# Led_panel_0_2.net
KiCad netlist of a schematic drawn in Altium Designer
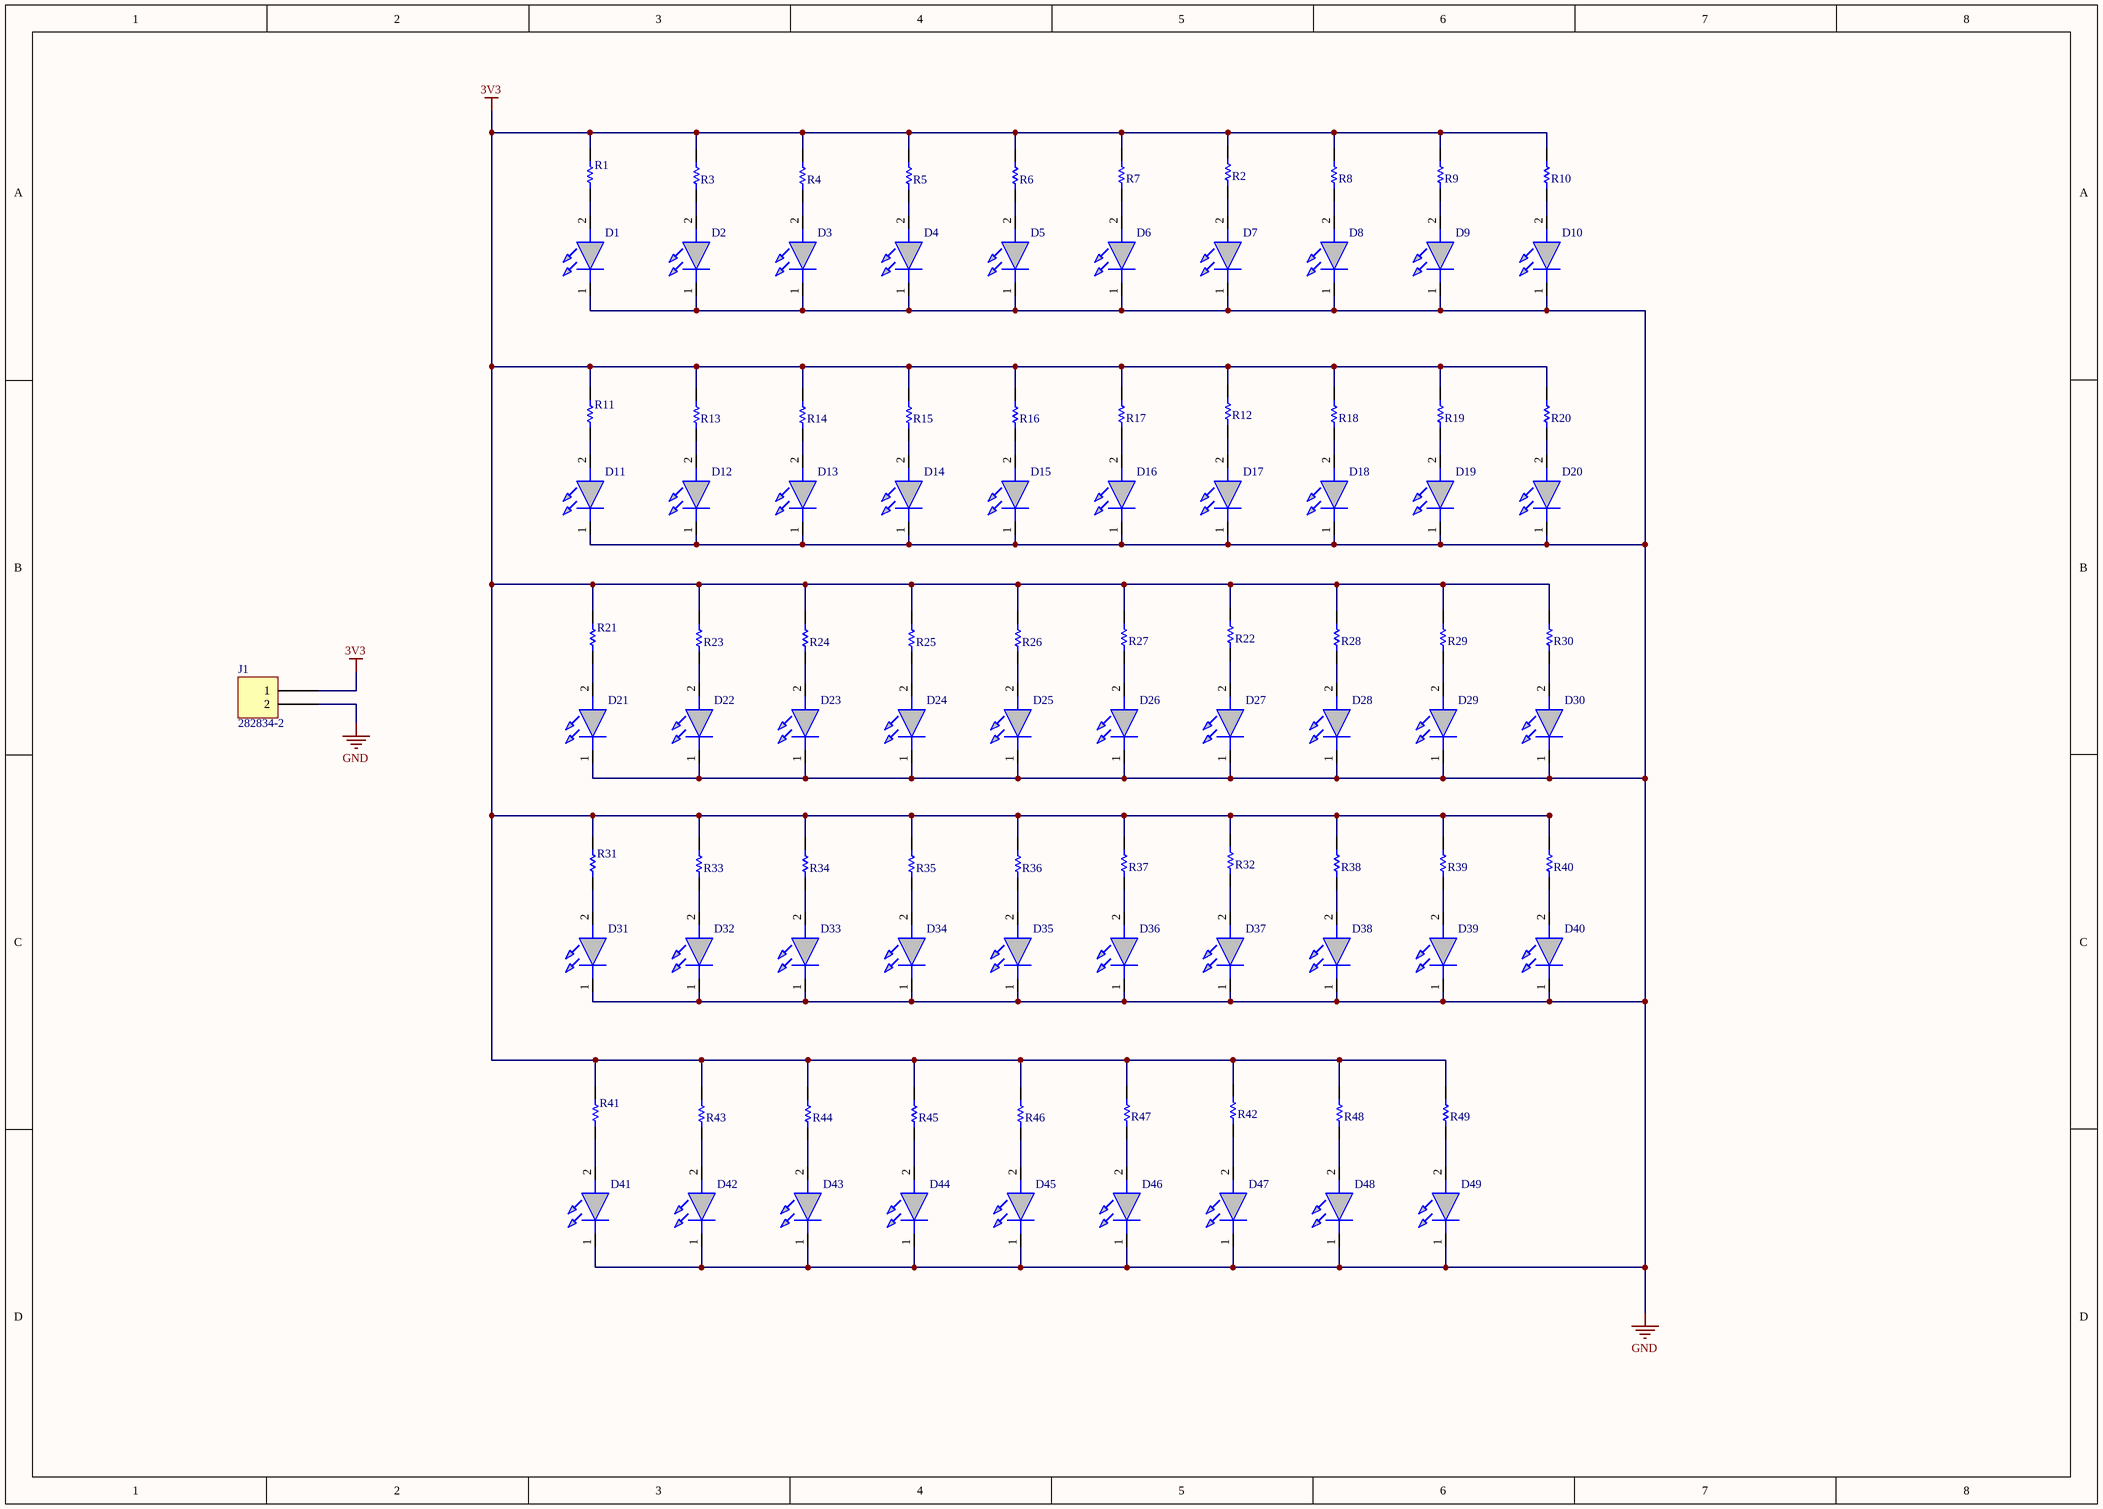
[diagram p0: Led panel 0.2.SchDoc]

(export (version "E")
  (design (tool "Eeschema 10.0.6"))
  (components
    (comp (ref "D1")
      (value "L1IG-0750100000000")
      (footprint "L1IG0750100000000")
      (description "Infrared Emitters - High Power Broadrange IR LED 600 - 1050nm")
      (fields (field (name "MOUSER PART NUMBER") "997-L1IG075010000"))
      (libsource (lib "L1IG-0750100000000") (part "L1IG-0750100000000"))
    )
    (comp (ref "D2")
      (value "L1IG-0750100000000")
      (footprint "L1IG0750100000000")
      (description "Infrared Emitters - High Power Broadrange IR LED 600 - 1050nm")
      (fields (field (name "MOUSER PART NUMBER") "997-L1IG075010000"))
      (libsource (lib "L1IG-0750100000000") (part "L1IG-0750100000000"))
    )
    (comp (ref "D3")
      (value "L1IG-0750100000000")
      (footprint "L1IG0750100000000")
      (description "Infrared Emitters - High Power Broadrange IR LED 600 - 1050nm")
      (fields (field (name "MOUSER PART NUMBER") "997-L1IG075010000"))
      (libsource (lib "L1IG-0750100000000") (part "L1IG-0750100000000"))
    )
    (comp (ref "D4")
      (value "L1IG-0750100000000")
      (footprint "L1IG0750100000000")
      (description "Infrared Emitters - High Power Broadrange IR LED 600 - 1050nm")
      (fields (field (name "MOUSER PART NUMBER") "997-L1IG075010000"))
      (libsource (lib "L1IG-0750100000000") (part "L1IG-0750100000000"))
    )
    (comp (ref "D5")
      (value "L1IG-0750100000000")
      (footprint "L1IG0750100000000")
      (description "Infrared Emitters - High Power Broadrange IR LED 600 - 1050nm")
      (fields (field (name "MOUSER PART NUMBER") "997-L1IG075010000"))
      (libsource (lib "L1IG-0750100000000") (part "L1IG-0750100000000"))
    )
    (comp (ref "D6")
      (value "L1IG-0750100000000")
      (footprint "L1IG0750100000000")
      (description "Infrared Emitters - High Power Broadrange IR LED 600 - 1050nm")
      (fields (field (name "MOUSER PART NUMBER") "997-L1IG075010000"))
      (libsource (lib "L1IG-0750100000000") (part "L1IG-0750100000000"))
    )
    (comp (ref "D7")
      (value "L1IG-0750100000000")
      (footprint "L1IG0750100000000")
      (description "Infrared Emitters - High Power Broadrange IR LED 600 - 1050nm")
      (fields (field (name "MOUSER PART NUMBER") "997-L1IG075010000"))
      (libsource (lib "L1IG-0750100000000") (part "L1IG-0750100000000"))
    )
    (comp (ref "D8")
      (value "L1IG-0750100000000")
      (footprint "L1IG0750100000000")
      (description "Infrared Emitters - High Power Broadrange IR LED 600 - 1050nm")
      (fields (field (name "MOUSER PART NUMBER") "997-L1IG075010000"))
      (libsource (lib "L1IG-0750100000000") (part "L1IG-0750100000000"))
    )
    (comp (ref "D9")
      (value "L1IG-0750100000000")
      (footprint "L1IG0750100000000")
      (description "Infrared Emitters - High Power Broadrange IR LED 600 - 1050nm")
      (fields (field (name "MOUSER PART NUMBER") "997-L1IG075010000"))
      (libsource (lib "L1IG-0750100000000") (part "L1IG-0750100000000"))
    )
    (comp (ref "D10")
      (value "L1IG-0750100000000")
      (footprint "L1IG0750100000000")
      (description "Infrared Emitters - High Power Broadrange IR LED 600 - 1050nm")
      (fields (field (name "MOUSER PART NUMBER") "997-L1IG075010000"))
      (libsource (lib "L1IG-0750100000000") (part "L1IG-0750100000000"))
    )
    (comp (ref "D11")
      (value "L1IG-0750100000000")
      (footprint "L1IG0750100000000")
      (description "Infrared Emitters - High Power Broadrange IR LED 600 - 1050nm")
      (fields (field (name "MOUSER PART NUMBER") "997-L1IG075010000"))
      (libsource (lib "L1IG-0750100000000") (part "L1IG-0750100000000"))
    )
    (comp (ref "D12")
      (value "L1IG-0750100000000")
      (footprint "L1IG0750100000000")
      (description "Infrared Emitters - High Power Broadrange IR LED 600 - 1050nm")
      (fields (field (name "MOUSER PART NUMBER") "997-L1IG075010000"))
      (libsource (lib "L1IG-0750100000000") (part "L1IG-0750100000000"))
    )
    (comp (ref "D13")
      (value "L1IG-0750100000000")
      (footprint "L1IG0750100000000")
      (description "Infrared Emitters - High Power Broadrange IR LED 600 - 1050nm")
      (fields (field (name "MOUSER PART NUMBER") "997-L1IG075010000"))
      (libsource (lib "L1IG-0750100000000") (part "L1IG-0750100000000"))
    )
    (comp (ref "D14")
      (value "L1IG-0750100000000")
      (footprint "L1IG0750100000000")
      (description "Infrared Emitters - High Power Broadrange IR LED 600 - 1050nm")
      (fields (field (name "MOUSER PART NUMBER") "997-L1IG075010000"))
      (libsource (lib "L1IG-0750100000000") (part "L1IG-0750100000000"))
    )
    (comp (ref "D15")
      (value "L1IG-0750100000000")
      (footprint "L1IG0750100000000")
      (description "Infrared Emitters - High Power Broadrange IR LED 600 - 1050nm")
      (fields (field (name "MOUSER PART NUMBER") "997-L1IG075010000"))
      (libsource (lib "L1IG-0750100000000") (part "L1IG-0750100000000"))
    )
    (comp (ref "D16")
      (value "L1IG-0750100000000")
      (footprint "L1IG0750100000000")
      (description "Infrared Emitters - High Power Broadrange IR LED 600 - 1050nm")
      (fields (field (name "MOUSER PART NUMBER") "997-L1IG075010000"))
      (libsource (lib "L1IG-0750100000000") (part "L1IG-0750100000000"))
    )
    (comp (ref "D17")
      (value "L1IG-0750100000000")
      (footprint "L1IG0750100000000")
      (description "Infrared Emitters - High Power Broadrange IR LED 600 - 1050nm")
      (fields (field (name "MOUSER PART NUMBER") "997-L1IG075010000"))
      (libsource (lib "L1IG-0750100000000") (part "L1IG-0750100000000"))
    )
    (comp (ref "D18")
      (value "L1IG-0750100000000")
      (footprint "L1IG0750100000000")
      (description "Infrared Emitters - High Power Broadrange IR LED 600 - 1050nm")
      (fields (field (name "MOUSER PART NUMBER") "997-L1IG075010000"))
      (libsource (lib "L1IG-0750100000000") (part "L1IG-0750100000000"))
    )
    (comp (ref "D19")
      (value "L1IG-0750100000000")
      (footprint "L1IG0750100000000")
      (description "Infrared Emitters - High Power Broadrange IR LED 600 - 1050nm")
      (fields (field (name "MOUSER PART NUMBER") "997-L1IG075010000"))
      (libsource (lib "L1IG-0750100000000") (part "L1IG-0750100000000"))
    )
    (comp (ref "D20")
      (value "L1IG-0750100000000")
      (footprint "L1IG0750100000000")
      (description "Infrared Emitters - High Power Broadrange IR LED 600 - 1050nm")
      (fields (field (name "MOUSER PART NUMBER") "997-L1IG075010000"))
      (libsource (lib "L1IG-0750100000000") (part "L1IG-0750100000000"))
    )
    (comp (ref "D21")
      (value "L1IG-0750100000000")
      (footprint "L1IG0750100000000")
      (description "Infrared Emitters - High Power Broadrange IR LED 600 - 1050nm")
      (fields (field (name "MOUSER PART NUMBER") "997-L1IG075010000"))
      (libsource (lib "L1IG-0750100000000") (part "L1IG-0750100000000"))
    )
    (comp (ref "D22")
      (value "L1IG-0750100000000")
      (footprint "L1IG0750100000000")
      (description "Infrared Emitters - High Power Broadrange IR LED 600 - 1050nm")
      (fields (field (name "MOUSER PART NUMBER") "997-L1IG075010000"))
      (libsource (lib "L1IG-0750100000000") (part "L1IG-0750100000000"))
    )
    (comp (ref "D23")
      (value "L1IG-0750100000000")
      (footprint "L1IG0750100000000")
      (description "Infrared Emitters - High Power Broadrange IR LED 600 - 1050nm")
      (fields (field (name "MOUSER PART NUMBER") "997-L1IG075010000"))
      (libsource (lib "L1IG-0750100000000") (part "L1IG-0750100000000"))
    )
    (comp (ref "D24")
      (value "L1IG-0750100000000")
      (footprint "L1IG0750100000000")
      (description "Infrared Emitters - High Power Broadrange IR LED 600 - 1050nm")
      (fields (field (name "MOUSER PART NUMBER") "997-L1IG075010000"))
      (libsource (lib "L1IG-0750100000000") (part "L1IG-0750100000000"))
    )
    (comp (ref "D25")
      (value "L1IG-0750100000000")
      (footprint "L1IG0750100000000")
      (description "Infrared Emitters - High Power Broadrange IR LED 600 - 1050nm")
      (fields (field (name "MOUSER PART NUMBER") "997-L1IG075010000"))
      (libsource (lib "L1IG-0750100000000") (part "L1IG-0750100000000"))
    )
    (comp (ref "D26")
      (value "L1IG-0750100000000")
      (footprint "L1IG0750100000000")
      (description "Infrared Emitters - High Power Broadrange IR LED 600 - 1050nm")
      (fields (field (name "MOUSER PART NUMBER") "997-L1IG075010000"))
      (libsource (lib "L1IG-0750100000000") (part "L1IG-0750100000000"))
    )
    (comp (ref "D27")
      (value "L1IG-0750100000000")
      (footprint "L1IG0750100000000")
      (description "Infrared Emitters - High Power Broadrange IR LED 600 - 1050nm")
      (fields (field (name "MOUSER PART NUMBER") "997-L1IG075010000"))
      (libsource (lib "L1IG-0750100000000") (part "L1IG-0750100000000"))
    )
    (comp (ref "D28")
      (value "L1IG-0750100000000")
      (footprint "L1IG0750100000000")
      (description "Infrared Emitters - High Power Broadrange IR LED 600 - 1050nm")
      (fields (field (name "MOUSER PART NUMBER") "997-L1IG075010000"))
      (libsource (lib "L1IG-0750100000000") (part "L1IG-0750100000000"))
    )
    (comp (ref "D29")
      (value "L1IG-0750100000000")
      (footprint "L1IG0750100000000")
      (description "Infrared Emitters - High Power Broadrange IR LED 600 - 1050nm")
      (fields (field (name "MOUSER PART NUMBER") "997-L1IG075010000"))
      (libsource (lib "L1IG-0750100000000") (part "L1IG-0750100000000"))
    )
    (comp (ref "D30")
      (value "L1IG-0750100000000")
      (footprint "L1IG0750100000000")
      (description "Infrared Emitters - High Power Broadrange IR LED 600 - 1050nm")
      (fields (field (name "MOUSER PART NUMBER") "997-L1IG075010000"))
      (libsource (lib "L1IG-0750100000000") (part "L1IG-0750100000000"))
    )
    (comp (ref "D31")
      (value "L1IG-0750100000000")
      (footprint "L1IG0750100000000")
      (description "Infrared Emitters - High Power Broadrange IR LED 600 - 1050nm")
      (fields (field (name "MOUSER PART NUMBER") "997-L1IG075010000"))
      (libsource (lib "L1IG-0750100000000") (part "L1IG-0750100000000"))
    )
    (comp (ref "D32")
      (value "L1IG-0750100000000")
      (footprint "L1IG0750100000000")
      (description "Infrared Emitters - High Power Broadrange IR LED 600 - 1050nm")
      (fields (field (name "MOUSER PART NUMBER") "997-L1IG075010000"))
      (libsource (lib "L1IG-0750100000000") (part "L1IG-0750100000000"))
    )
    (comp (ref "D33")
      (value "L1IG-0750100000000")
      (footprint "L1IG0750100000000")
      (description "Infrared Emitters - High Power Broadrange IR LED 600 - 1050nm")
      (fields (field (name "MOUSER PART NUMBER") "997-L1IG075010000"))
      (libsource (lib "L1IG-0750100000000") (part "L1IG-0750100000000"))
    )
    (comp (ref "D34")
      (value "L1IG-0750100000000")
      (footprint "L1IG0750100000000")
      (description "Infrared Emitters - High Power Broadrange IR LED 600 - 1050nm")
      (fields (field (name "MOUSER PART NUMBER") "997-L1IG075010000"))
      (libsource (lib "L1IG-0750100000000") (part "L1IG-0750100000000"))
    )
    (comp (ref "D35")
      (value "L1IG-0750100000000")
      (footprint "L1IG0750100000000")
      (description "Infrared Emitters - High Power Broadrange IR LED 600 - 1050nm")
      (fields (field (name "MOUSER PART NUMBER") "997-L1IG075010000"))
      (libsource (lib "L1IG-0750100000000") (part "L1IG-0750100000000"))
    )
    (comp (ref "D36")
      (value "L1IG-0750100000000")
      (footprint "L1IG0750100000000")
      (description "Infrared Emitters - High Power Broadrange IR LED 600 - 1050nm")
      (fields (field (name "MOUSER PART NUMBER") "997-L1IG075010000"))
      (libsource (lib "L1IG-0750100000000") (part "L1IG-0750100000000"))
    )
    (comp (ref "D37")
      (value "L1IG-0750100000000")
      (footprint "L1IG0750100000000")
      (description "Infrared Emitters - High Power Broadrange IR LED 600 - 1050nm")
      (fields (field (name "MOUSER PART NUMBER") "997-L1IG075010000"))
      (libsource (lib "L1IG-0750100000000") (part "L1IG-0750100000000"))
    )
    (comp (ref "D38")
      (value "L1IG-0750100000000")
      (footprint "L1IG0750100000000")
      (description "Infrared Emitters - High Power Broadrange IR LED 600 - 1050nm")
      (fields (field (name "MOUSER PART NUMBER") "997-L1IG075010000"))
      (libsource (lib "L1IG-0750100000000") (part "L1IG-0750100000000"))
    )
    (comp (ref "D39")
      (value "L1IG-0750100000000")
      (footprint "L1IG0750100000000")
      (description "Infrared Emitters - High Power Broadrange IR LED 600 - 1050nm")
      (fields (field (name "MOUSER PART NUMBER") "997-L1IG075010000"))
      (libsource (lib "L1IG-0750100000000") (part "L1IG-0750100000000"))
    )
    (comp (ref "D40")
      (value "L1IG-0750100000000")
      (footprint "L1IG0750100000000")
      (description "Infrared Emitters - High Power Broadrange IR LED 600 - 1050nm")
      (fields (field (name "MOUSER PART NUMBER") "997-L1IG075010000"))
      (libsource (lib "L1IG-0750100000000") (part "L1IG-0750100000000"))
    )
    (comp (ref "D41")
      (value "L1IG-0750100000000")
      (footprint "L1IG0750100000000")
      (description "Infrared Emitters - High Power Broadrange IR LED 600 - 1050nm")
      (fields (field (name "MOUSER PART NUMBER") "997-L1IG075010000"))
      (libsource (lib "L1IG-0750100000000") (part "L1IG-0750100000000"))
    )
    (comp (ref "D42")
      (value "L1IG-0750100000000")
      (footprint "L1IG0750100000000")
      (description "Infrared Emitters - High Power Broadrange IR LED 600 - 1050nm")
      (fields (field (name "MOUSER PART NUMBER") "997-L1IG075010000"))
      (libsource (lib "L1IG-0750100000000") (part "L1IG-0750100000000"))
    )
    (comp (ref "D43")
      (value "L1IG-0750100000000")
      (footprint "L1IG0750100000000")
      (description "Infrared Emitters - High Power Broadrange IR LED 600 - 1050nm")
      (fields (field (name "MOUSER PART NUMBER") "997-L1IG075010000"))
      (libsource (lib "L1IG-0750100000000") (part "L1IG-0750100000000"))
    )
    (comp (ref "D44")
      (value "L1IG-0750100000000")
      (footprint "L1IG0750100000000")
      (description "Infrared Emitters - High Power Broadrange IR LED 600 - 1050nm")
      (fields (field (name "MOUSER PART NUMBER") "997-L1IG075010000"))
      (libsource (lib "L1IG-0750100000000") (part "L1IG-0750100000000"))
    )
    (comp (ref "D45")
      (value "L1IG-0750100000000")
      (footprint "L1IG0750100000000")
      (description "Infrared Emitters - High Power Broadrange IR LED 600 - 1050nm")
      (fields (field (name "MOUSER PART NUMBER") "997-L1IG075010000"))
      (libsource (lib "L1IG-0750100000000") (part "L1IG-0750100000000"))
    )
    (comp (ref "D46")
      (value "L1IG-0750100000000")
      (footprint "L1IG0750100000000")
      (description "Infrared Emitters - High Power Broadrange IR LED 600 - 1050nm")
      (fields (field (name "MOUSER PART NUMBER") "997-L1IG075010000"))
      (libsource (lib "L1IG-0750100000000") (part "L1IG-0750100000000"))
    )
    (comp (ref "D47")
      (value "L1IG-0750100000000")
      (footprint "L1IG0750100000000")
      (description "Infrared Emitters - High Power Broadrange IR LED 600 - 1050nm")
      (fields (field (name "MOUSER PART NUMBER") "997-L1IG075010000"))
      (libsource (lib "L1IG-0750100000000") (part "L1IG-0750100000000"))
    )
    (comp (ref "D48")
      (value "L1IG-0750100000000")
      (footprint "L1IG0750100000000")
      (description "Infrared Emitters - High Power Broadrange IR LED 600 - 1050nm")
      (fields (field (name "MOUSER PART NUMBER") "997-L1IG075010000"))
      (libsource (lib "L1IG-0750100000000") (part "L1IG-0750100000000"))
    )
    (comp (ref "D49")
      (value "L1IG-0750100000000")
      (footprint "L1IG0750100000000")
      (description "Infrared Emitters - High Power Broadrange IR LED 600 - 1050nm")
      (fields (field (name "MOUSER PART NUMBER") "997-L1IG075010000"))
      (libsource (lib "L1IG-0750100000000") (part "L1IG-0750100000000"))
    )
    (comp (ref "J1")
      (value "282834-2")
      (footprint "TE 282834-2")
      (description "TERM BLK 2P SIDE ENT 2.54MM PCB")
      (fields (field (name "MANUFACTURER") "TE Connectivity AMP Connectors") (field (name "VOLTAGE") "150V"))
      (libsource (lib "Celestial Altium Library - altium_library") (part "2 Pin"))
    )
    (comp (ref "R1")
      (value "RC0805FR-0710KL")
      (footprint "RESC2013X60X35NL10T20")
      (description "Chip Resistor, 10 KOhm, +/- 1%, 0.125 W, -55 to 155 degC, 0805 (2012 Metric), RoHS, Tape and Reel")
      (fields (field (name "MANUFACTURER") "Yageo"))
      (libsource (lib "Altium Content Vault") (part "RES-2"))
    )
    (comp (ref "R2")
      (value "RC0805FR-0710KL")
      (footprint "RESC2013X60X35NL10T20")
      (description "Chip Resistor, 10 KOhm, +/- 1%, 0.125 W, -55 to 155 degC, 0805 (2012 Metric), RoHS, Tape and Reel")
      (fields (field (name "MANUFACTURER") "Yageo"))
      (libsource (lib "Altium Content Vault") (part "RES-2"))
    )
    (comp (ref "R3")
      (value "RC0805FR-0710KL")
      (footprint "RESC2013X60X35NL10T20")
      (description "Chip Resistor, 10 KOhm, +/- 1%, 0.125 W, -55 to 155 degC, 0805 (2012 Metric), RoHS, Tape and Reel")
      (fields (field (name "MANUFACTURER") "Yageo"))
      (libsource (lib "Altium Content Vault") (part "RES-2"))
    )
    (comp (ref "R4")
      (value "RC0805FR-0710KL")
      (footprint "RESC2013X60X35NL10T20")
      (description "Chip Resistor, 10 KOhm, +/- 1%, 0.125 W, -55 to 155 degC, 0805 (2012 Metric), RoHS, Tape and Reel")
      (fields (field (name "MANUFACTURER") "Yageo"))
      (libsource (lib "Altium Content Vault") (part "RES-2"))
    )
    (comp (ref "R5")
      (value "RC0805FR-0710KL")
      (footprint "RESC2013X60X35NL10T20")
      (description "Chip Resistor, 10 KOhm, +/- 1%, 0.125 W, -55 to 155 degC, 0805 (2012 Metric), RoHS, Tape and Reel")
      (fields (field (name "MANUFACTURER") "Yageo"))
      (libsource (lib "Altium Content Vault") (part "RES-2"))
    )
    (comp (ref "R6")
      (value "RC0805FR-0710KL")
      (footprint "RESC2013X60X35NL10T20")
      (description "Chip Resistor, 10 KOhm, +/- 1%, 0.125 W, -55 to 155 degC, 0805 (2012 Metric), RoHS, Tape and Reel")
      (fields (field (name "MANUFACTURER") "Yageo"))
      (libsource (lib "Altium Content Vault") (part "RES-2"))
    )
    (comp (ref "R7")
      (value "RC0805FR-0710KL")
      (footprint "RESC2013X60X35NL10T20")
      (description "Chip Resistor, 10 KOhm, +/- 1%, 0.125 W, -55 to 155 degC, 0805 (2012 Metric), RoHS, Tape and Reel")
      (fields (field (name "MANUFACTURER") "Yageo"))
      (libsource (lib "Altium Content Vault") (part "RES-2"))
    )
    (comp (ref "R8")
      (value "RC0805FR-0710KL")
      (footprint "RESC2013X60X35NL10T20")
      (description "Chip Resistor, 10 KOhm, +/- 1%, 0.125 W, -55 to 155 degC, 0805 (2012 Metric), RoHS, Tape and Reel")
      (fields (field (name "MANUFACTURER") "Yageo"))
      (libsource (lib "Altium Content Vault") (part "RES-2"))
    )
    (comp (ref "R9")
      (value "RC0805FR-0710KL")
      (footprint "RESC2013X60X35NL10T20")
      (description "Chip Resistor, 10 KOhm, +/- 1%, 0.125 W, -55 to 155 degC, 0805 (2012 Metric), RoHS, Tape and Reel")
      (fields (field (name "MANUFACTURER") "Yageo"))
      (libsource (lib "Altium Content Vault") (part "RES-2"))
    )
    (comp (ref "R10")
      (value "RC0805FR-0710KL")
      (footprint "RESC2013X60X35NL10T20")
      (description "Chip Resistor, 10 KOhm, +/- 1%, 0.125 W, -55 to 155 degC, 0805 (2012 Metric), RoHS, Tape and Reel")
      (fields (field (name "MANUFACTURER") "Yageo"))
      (libsource (lib "Altium Content Vault") (part "RES-2"))
    )
    (comp (ref "R11")
      (value "RC0805FR-0710KL")
      (footprint "RESC2013X60X35NL10T20")
      (description "Chip Resistor, 10 KOhm, +/- 1%, 0.125 W, -55 to 155 degC, 0805 (2012 Metric), RoHS, Tape and Reel")
      (fields (field (name "MANUFACTURER") "Yageo"))
      (libsource (lib "Altium Content Vault") (part "RES-2"))
    )
    (comp (ref "R12")
      (value "RC0805FR-0710KL")
      (footprint "RESC2013X60X35NL10T20")
      (description "Chip Resistor, 10 KOhm, +/- 1%, 0.125 W, -55 to 155 degC, 0805 (2012 Metric), RoHS, Tape and Reel")
      (fields (field (name "MANUFACTURER") "Yageo"))
      (libsource (lib "Altium Content Vault") (part "RES-2"))
    )
    (comp (ref "R13")
      (value "RC0805FR-0710KL")
      (footprint "RESC2013X60X35NL10T20")
      (description "Chip Resistor, 10 KOhm, +/- 1%, 0.125 W, -55 to 155 degC, 0805 (2012 Metric), RoHS, Tape and Reel")
      (fields (field (name "MANUFACTURER") "Yageo"))
      (libsource (lib "Altium Content Vault") (part "RES-2"))
    )
    (comp (ref "R14")
      (value "RC0805FR-0710KL")
      (footprint "RESC2013X60X35NL10T20")
      (description "Chip Resistor, 10 KOhm, +/- 1%, 0.125 W, -55 to 155 degC, 0805 (2012 Metric), RoHS, Tape and Reel")
      (fields (field (name "MANUFACTURER") "Yageo"))
      (libsource (lib "Altium Content Vault") (part "RES-2"))
    )
    (comp (ref "R15")
      (value "RC0805FR-0710KL")
      (footprint "RESC2013X60X35NL10T20")
      (description "Chip Resistor, 10 KOhm, +/- 1%, 0.125 W, -55 to 155 degC, 0805 (2012 Metric), RoHS, Tape and Reel")
      (fields (field (name "MANUFACTURER") "Yageo"))
      (libsource (lib "Altium Content Vault") (part "RES-2"))
    )
    (comp (ref "R16")
      (value "RC0805FR-0710KL")
      (footprint "RESC2013X60X35NL10T20")
      (description "Chip Resistor, 10 KOhm, +/- 1%, 0.125 W, -55 to 155 degC, 0805 (2012 Metric), RoHS, Tape and Reel")
      (fields (field (name "MANUFACTURER") "Yageo"))
      (libsource (lib "Altium Content Vault") (part "RES-2"))
    )
    (comp (ref "R17")
      (value "RC0805FR-0710KL")
      (footprint "RESC2013X60X35NL10T20")
      (description "Chip Resistor, 10 KOhm, +/- 1%, 0.125 W, -55 to 155 degC, 0805 (2012 Metric), RoHS, Tape and Reel")
      (fields (field (name "MANUFACTURER") "Yageo"))
      (libsource (lib "Altium Content Vault") (part "RES-2"))
    )
    (comp (ref "R18")
      (value "RC0805FR-0710KL")
      (footprint "RESC2013X60X35NL10T20")
      (description "Chip Resistor, 10 KOhm, +/- 1%, 0.125 W, -55 to 155 degC, 0805 (2012 Metric), RoHS, Tape and Reel")
      (fields (field (name "MANUFACTURER") "Yageo"))
      (libsource (lib "Altium Content Vault") (part "RES-2"))
    )
    (comp (ref "R19")
      (value "RC0805FR-0710KL")
      (footprint "RESC2013X60X35NL10T20")
      (description "Chip Resistor, 10 KOhm, +/- 1%, 0.125 W, -55 to 155 degC, 0805 (2012 Metric), RoHS, Tape and Reel")
      (fields (field (name "MANUFACTURER") "Yageo"))
      (libsource (lib "Altium Content Vault") (part "RES-2"))
    )
    (comp (ref "R20")
      (value "RC0805FR-0710KL")
      (footprint "RESC2013X60X35NL10T20")
      (description "Chip Resistor, 10 KOhm, +/- 1%, 0.125 W, -55 to 155 degC, 0805 (2012 Metric), RoHS, Tape and Reel")
      (fields (field (name "MANUFACTURER") "Yageo"))
      (libsource (lib "Altium Content Vault") (part "RES-2"))
    )
    (comp (ref "R21")
      (value "RC0805FR-0710KL")
      (footprint "RESC2013X60X35NL10T20")
      (description "Chip Resistor, 10 KOhm, +/- 1%, 0.125 W, -55 to 155 degC, 0805 (2012 Metric), RoHS, Tape and Reel")
      (fields (field (name "MANUFACTURER") "Yageo"))
      (libsource (lib "Altium Content Vault") (part "RES-2"))
    )
    (comp (ref "R22")
      (value "RC0805FR-0710KL")
      (footprint "RESC2013X60X35NL10T20")
      (description "Chip Resistor, 10 KOhm, +/- 1%, 0.125 W, -55 to 155 degC, 0805 (2012 Metric), RoHS, Tape and Reel")
      (fields (field (name "MANUFACTURER") "Yageo"))
      (libsource (lib "Altium Content Vault") (part "RES-2"))
    )
    (comp (ref "R23")
      (value "RC0805FR-0710KL")
      (footprint "RESC2013X60X35NL10T20")
      (description "Chip Resistor, 10 KOhm, +/- 1%, 0.125 W, -55 to 155 degC, 0805 (2012 Metric), RoHS, Tape and Reel")
      (fields (field (name "MANUFACTURER") "Yageo"))
      (libsource (lib "Altium Content Vault") (part "RES-2"))
    )
    (comp (ref "R24")
      (value "RC0805FR-0710KL")
      (footprint "RESC2013X60X35NL10T20")
      (description "Chip Resistor, 10 KOhm, +/- 1%, 0.125 W, -55 to 155 degC, 0805 (2012 Metric), RoHS, Tape and Reel")
      (fields (field (name "MANUFACTURER") "Yageo"))
      (libsource (lib "Altium Content Vault") (part "RES-2"))
    )
    (comp (ref "R25")
      (value "RC0805FR-0710KL")
      (footprint "RESC2013X60X35NL10T20")
      (description "Chip Resistor, 10 KOhm, +/- 1%, 0.125 W, -55 to 155 degC, 0805 (2012 Metric), RoHS, Tape and Reel")
      (fields (field (name "MANUFACTURER") "Yageo"))
      (libsource (lib "Altium Content Vault") (part "RES-2"))
    )
    (comp (ref "R26")
      (value "RC0805FR-0710KL")
      (footprint "RESC2013X60X35NL10T20")
      (description "Chip Resistor, 10 KOhm, +/- 1%, 0.125 W, -55 to 155 degC, 0805 (2012 Metric), RoHS, Tape and Reel")
      (fields (field (name "MANUFACTURER") "Yageo"))
      (libsource (lib "Altium Content Vault") (part "RES-2"))
    )
    (comp (ref "R27")
      (value "RC0805FR-0710KL")
      (footprint "RESC2013X60X35NL10T20")
      (description "Chip Resistor, 10 KOhm, +/- 1%, 0.125 W, -55 to 155 degC, 0805 (2012 Metric), RoHS, Tape and Reel")
      (fields (field (name "MANUFACTURER") "Yageo"))
      (libsource (lib "Altium Content Vault") (part "RES-2"))
    )
    (comp (ref "R28")
      (value "RC0805FR-0710KL")
      (footprint "RESC2013X60X35NL10T20")
      (description "Chip Resistor, 10 KOhm, +/- 1%, 0.125 W, -55 to 155 degC, 0805 (2012 Metric), RoHS, Tape and Reel")
      (fields (field (name "MANUFACTURER") "Yageo"))
      (libsource (lib "Altium Content Vault") (part "RES-2"))
    )
    (comp (ref "R29")
      (value "RC0805FR-0710KL")
      (footprint "RESC2013X60X35NL10T20")
      (description "Chip Resistor, 10 KOhm, +/- 1%, 0.125 W, -55 to 155 degC, 0805 (2012 Metric), RoHS, Tape and Reel")
      (fields (field (name "MANUFACTURER") "Yageo"))
      (libsource (lib "Altium Content Vault") (part "RES-2"))
    )
    (comp (ref "R30")
      (value "RC0805FR-0710KL")
      (footprint "RESC2013X60X35NL10T20")
      (description "Chip Resistor, 10 KOhm, +/- 1%, 0.125 W, -55 to 155 degC, 0805 (2012 Metric), RoHS, Tape and Reel")
      (fields (field (name "MANUFACTURER") "Yageo"))
      (libsource (lib "Altium Content Vault") (part "RES-2"))
    )
    (comp (ref "R31")
      (value "RC0805FR-0710KL")
      (footprint "RESC2013X60X35NL10T20")
      (description "Chip Resistor, 10 KOhm, +/- 1%, 0.125 W, -55 to 155 degC, 0805 (2012 Metric), RoHS, Tape and Reel")
      (fields (field (name "MANUFACTURER") "Yageo"))
      (libsource (lib "Altium Content Vault") (part "RES-2"))
    )
    (comp (ref "R32")
      (value "RC0805FR-0710KL")
      (footprint "RESC2013X60X35NL10T20")
      (description "Chip Resistor, 10 KOhm, +/- 1%, 0.125 W, -55 to 155 degC, 0805 (2012 Metric), RoHS, Tape and Reel")
      (fields (field (name "MANUFACTURER") "Yageo"))
      (libsource (lib "Altium Content Vault") (part "RES-2"))
    )
    (comp (ref "R33")
      (value "RC0805FR-0710KL")
      (footprint "RESC2013X60X35NL10T20")
      (description "Chip Resistor, 10 KOhm, +/- 1%, 0.125 W, -55 to 155 degC, 0805 (2012 Metric), RoHS, Tape and Reel")
      (fields (field (name "MANUFACTURER") "Yageo"))
      (libsource (lib "Altium Content Vault") (part "RES-2"))
    )
    (comp (ref "R34")
      (value "RC0805FR-0710KL")
      (footprint "RESC2013X60X35NL10T20")
      (description "Chip Resistor, 10 KOhm, +/- 1%, 0.125 W, -55 to 155 degC, 0805 (2012 Metric), RoHS, Tape and Reel")
      (fields (field (name "MANUFACTURER") "Yageo"))
      (libsource (lib "Altium Content Vault") (part "RES-2"))
    )
    (comp (ref "R35")
      (value "RC0805FR-0710KL")
      (footprint "RESC2013X60X35NL10T20")
      (description "Chip Resistor, 10 KOhm, +/- 1%, 0.125 W, -55 to 155 degC, 0805 (2012 Metric), RoHS, Tape and Reel")
      (fields (field (name "MANUFACTURER") "Yageo"))
      (libsource (lib "Altium Content Vault") (part "RES-2"))
    )
    (comp (ref "R36")
      (value "RC0805FR-0710KL")
      (footprint "RESC2013X60X35NL10T20")
      (description "Chip Resistor, 10 KOhm, +/- 1%, 0.125 W, -55 to 155 degC, 0805 (2012 Metric), RoHS, Tape and Reel")
      (fields (field (name "MANUFACTURER") "Yageo"))
      (libsource (lib "Altium Content Vault") (part "RES-2"))
    )
    (comp (ref "R37")
      (value "RC0805FR-0710KL")
      (footprint "RESC2013X60X35NL10T20")
      (description "Chip Resistor, 10 KOhm, +/- 1%, 0.125 W, -55 to 155 degC, 0805 (2012 Metric), RoHS, Tape and Reel")
      (fields (field (name "MANUFACTURER") "Yageo"))
      (libsource (lib "Altium Content Vault") (part "RES-2"))
    )
    (comp (ref "R38")
      (value "RC0805FR-0710KL")
      (footprint "RESC2013X60X35NL10T20")
      (description "Chip Resistor, 10 KOhm, +/- 1%, 0.125 W, -55 to 155 degC, 0805 (2012 Metric), RoHS, Tape and Reel")
      (fields (field (name "MANUFACTURER") "Yageo"))
      (libsource (lib "Altium Content Vault") (part "RES-2"))
    )
    (comp (ref "R39")
      (value "RC0805FR-0710KL")
      (footprint "RESC2013X60X35NL10T20")
      (description "Chip Resistor, 10 KOhm, +/- 1%, 0.125 W, -55 to 155 degC, 0805 (2012 Metric), RoHS, Tape and Reel")
      (fields (field (name "MANUFACTURER") "Yageo"))
      (libsource (lib "Altium Content Vault") (part "RES-2"))
    )
    (comp (ref "R40")
      (value "RC0805FR-0710KL")
      (footprint "RESC2013X60X35NL10T20")
      (description "Chip Resistor, 10 KOhm, +/- 1%, 0.125 W, -55 to 155 degC, 0805 (2012 Metric), RoHS, Tape and Reel")
      (fields (field (name "MANUFACTURER") "Yageo"))
      (libsource (lib "Altium Content Vault") (part "RES-2"))
    )
    (comp (ref "R41")
      (value "RC0805FR-0710KL")
      (footprint "RESC2013X60X35NL10T20")
      (description "Chip Resistor, 10 KOhm, +/- 1%, 0.125 W, -55 to 155 degC, 0805 (2012 Metric), RoHS, Tape and Reel")
      (fields (field (name "MANUFACTURER") "Yageo"))
      (libsource (lib "Altium Content Vault") (part "RES-2"))
    )
    (comp (ref "R42")
      (value "RC0805FR-0710KL")
      (footprint "RESC2013X60X35NL10T20")
      (description "Chip Resistor, 10 KOhm, +/- 1%, 0.125 W, -55 to 155 degC, 0805 (2012 Metric), RoHS, Tape and Reel")
      (fields (field (name "MANUFACTURER") "Yageo"))
      (libsource (lib "Altium Content Vault") (part "RES-2"))
    )
    (comp (ref "R43")
      (value "RC0805FR-0710KL")
      (footprint "RESC2013X60X35NL10T20")
      (description "Chip Resistor, 10 KOhm, +/- 1%, 0.125 W, -55 to 155 degC, 0805 (2012 Metric), RoHS, Tape and Reel")
      (fields (field (name "MANUFACTURER") "Yageo"))
      (libsource (lib "Altium Content Vault") (part "RES-2"))
    )
    (comp (ref "R44")
      (value "RC0805FR-0710KL")
      (footprint "RESC2013X60X35NL10T20")
      (description "Chip Resistor, 10 KOhm, +/- 1%, 0.125 W, -55 to 155 degC, 0805 (2012 Metric), RoHS, Tape and Reel")
      (fields (field (name "MANUFACTURER") "Yageo"))
      (libsource (lib "Altium Content Vault") (part "RES-2"))
    )
    (comp (ref "R45")
      (value "RC0805FR-0710KL")
      (footprint "RESC2013X60X35NL10T20")
      (description "Chip Resistor, 10 KOhm, +/- 1%, 0.125 W, -55 to 155 degC, 0805 (2012 Metric), RoHS, Tape and Reel")
      (fields (field (name "MANUFACTURER") "Yageo"))
      (libsource (lib "Altium Content Vault") (part "RES-2"))
    )
    (comp (ref "R46")
      (value "RC0805FR-0710KL")
      (footprint "RESC2013X60X35NL10T20")
      (description "Chip Resistor, 10 KOhm, +/- 1%, 0.125 W, -55 to 155 degC, 0805 (2012 Metric), RoHS, Tape and Reel")
      (fields (field (name "MANUFACTURER") "Yageo"))
      (libsource (lib "Altium Content Vault") (part "RES-2"))
    )
    (comp (ref "R47")
      (value "RC0805FR-0710KL")
      (footprint "RESC2013X60X35NL10T20")
      (description "Chip Resistor, 10 KOhm, +/- 1%, 0.125 W, -55 to 155 degC, 0805 (2012 Metric), RoHS, Tape and Reel")
      (fields (field (name "MANUFACTURER") "Yageo"))
      (libsource (lib "Altium Content Vault") (part "RES-2"))
    )
    (comp (ref "R48")
      (value "RC0805FR-0710KL")
      (footprint "RESC2013X60X35NL10T20")
      (description "Chip Resistor, 10 KOhm, +/- 1%, 0.125 W, -55 to 155 degC, 0805 (2012 Metric), RoHS, Tape and Reel")
      (fields (field (name "MANUFACTURER") "Yageo"))
      (libsource (lib "Altium Content Vault") (part "RES-2"))
    )
    (comp (ref "R49")
      (value "RC0805FR-0710KL")
      (footprint "RESC2013X60X35NL10T20")
      (description "Chip Resistor, 10 KOhm, +/- 1%, 0.125 W, -55 to 155 degC, 0805 (2012 Metric), RoHS, Tape and Reel")
      (fields (field (name "MANUFACTURER") "Yageo"))
      (libsource (lib "Altium Content Vault") (part "RES-2"))
    )
  )
  (nets
    (net (code "1") (name "3V3") (class "Default")
      (node (ref "J1") (pin "1") (pinfunction "1_1") (pintype "passive"))
      (node (ref "R1") (pin "2") (pinfunction "2_2") (pintype "passive"))
      (node (ref "R10") (pin "2") (pinfunction "2_2") (pintype "passive"))
      (node (ref "R11") (pin "2") (pinfunction "2_2") (pintype "passive"))
      (node (ref "R12") (pin "2") (pinfunction "2_2") (pintype "passive"))
      (node (ref "R13") (pin "2") (pinfunction "2_2") (pintype "passive"))
      (node (ref "R14") (pin "2") (pinfunction "2_2") (pintype "passive"))
      (node (ref "R15") (pin "2") (pinfunction "2_2") (pintype "passive"))
      (node (ref "R16") (pin "2") (pinfunction "2_2") (pintype "passive"))
      (node (ref "R17") (pin "2") (pinfunction "2_2") (pintype "passive"))
      (node (ref "R18") (pin "2") (pinfunction "2_2") (pintype "passive"))
      (node (ref "R19") (pin "2") (pinfunction "2_2") (pintype "passive"))
      (node (ref "R2") (pin "2") (pinfunction "2_2") (pintype "passive"))
      (node (ref "R20") (pin "2") (pinfunction "2_2") (pintype "passive"))
      (node (ref "R21") (pin "2") (pinfunction "2_2") (pintype "passive"))
      (node (ref "R22") (pin "2") (pinfunction "2_2") (pintype "passive"))
      (node (ref "R23") (pin "2") (pinfunction "2_2") (pintype "passive"))
      (node (ref "R24") (pin "2") (pinfunction "2_2") (pintype "passive"))
      (node (ref "R25") (pin "2") (pinfunction "2_2") (pintype "passive"))
      (node (ref "R26") (pin "2") (pinfunction "2_2") (pintype "passive"))
      (node (ref "R27") (pin "2") (pinfunction "2_2") (pintype "passive"))
      (node (ref "R28") (pin "2") (pinfunction "2_2") (pintype "passive"))
      (node (ref "R29") (pin "2") (pinfunction "2_2") (pintype "passive"))
      (node (ref "R3") (pin "2") (pinfunction "2_2") (pintype "passive"))
      (node (ref "R30") (pin "2") (pinfunction "2_2") (pintype "passive"))
      (node (ref "R31") (pin "2") (pinfunction "2_2") (pintype "passive"))
      (node (ref "R32") (pin "2") (pinfunction "2_2") (pintype "passive"))
      (node (ref "R33") (pin "2") (pinfunction "2_2") (pintype "passive"))
      (node (ref "R34") (pin "2") (pinfunction "2_2") (pintype "passive"))
      (node (ref "R35") (pin "2") (pinfunction "2_2") (pintype "passive"))
      (node (ref "R36") (pin "2") (pinfunction "2_2") (pintype "passive"))
      (node (ref "R37") (pin "2") (pinfunction "2_2") (pintype "passive"))
      (node (ref "R38") (pin "2") (pinfunction "2_2") (pintype "passive"))
      (node (ref "R39") (pin "2") (pinfunction "2_2") (pintype "passive"))
      (node (ref "R4") (pin "2") (pinfunction "2_2") (pintype "passive"))
      (node (ref "R40") (pin "2") (pinfunction "2_2") (pintype "passive"))
      (node (ref "R41") (pin "2") (pinfunction "2_2") (pintype "passive"))
      (node (ref "R42") (pin "2") (pinfunction "2_2") (pintype "passive"))
      (node (ref "R43") (pin "2") (pinfunction "2_2") (pintype "passive"))
      (node (ref "R44") (pin "2") (pinfunction "2_2") (pintype "passive"))
      (node (ref "R45") (pin "2") (pinfunction "2_2") (pintype "passive"))
      (node (ref "R46") (pin "2") (pinfunction "2_2") (pintype "passive"))
      (node (ref "R47") (pin "2") (pinfunction "2_2") (pintype "passive"))
      (node (ref "R48") (pin "2") (pinfunction "2_2") (pintype "passive"))
      (node (ref "R49") (pin "2") (pinfunction "2_2") (pintype "passive"))
      (node (ref "R5") (pin "2") (pinfunction "2_2") (pintype "passive"))
      (node (ref "R6") (pin "2") (pinfunction "2_2") (pintype "passive"))
      (node (ref "R7") (pin "2") (pinfunction "2_2") (pintype "passive"))
      (node (ref "R8") (pin "2") (pinfunction "2_2") (pintype "passive"))
      (node (ref "R9") (pin "2") (pinfunction "2_2") (pintype "passive"))
    )
    (net (code "2") (name "GND") (class "Default")
      (node (ref "D1") (pin "1") (pinfunction "K_1") (pintype "passive"))
      (node (ref "D10") (pin "1") (pinfunction "K_1") (pintype "passive"))
      (node (ref "D11") (pin "1") (pinfunction "K_1") (pintype "passive"))
      (node (ref "D12") (pin "1") (pinfunction "K_1") (pintype "passive"))
      (node (ref "D13") (pin "1") (pinfunction "K_1") (pintype "passive"))
      (node (ref "D14") (pin "1") (pinfunction "K_1") (pintype "passive"))
      (node (ref "D15") (pin "1") (pinfunction "K_1") (pintype "passive"))
      (node (ref "D16") (pin "1") (pinfunction "K_1") (pintype "passive"))
      (node (ref "D17") (pin "1") (pinfunction "K_1") (pintype "passive"))
      (node (ref "D18") (pin "1") (pinfunction "K_1") (pintype "passive"))
      (node (ref "D19") (pin "1") (pinfunction "K_1") (pintype "passive"))
      (node (ref "D2") (pin "1") (pinfunction "K_1") (pintype "passive"))
      (node (ref "D20") (pin "1") (pinfunction "K_1") (pintype "passive"))
      (node (ref "D21") (pin "1") (pinfunction "K_1") (pintype "passive"))
      (node (ref "D22") (pin "1") (pinfunction "K_1") (pintype "passive"))
      (node (ref "D23") (pin "1") (pinfunction "K_1") (pintype "passive"))
      (node (ref "D24") (pin "1") (pinfunction "K_1") (pintype "passive"))
      (node (ref "D25") (pin "1") (pinfunction "K_1") (pintype "passive"))
      (node (ref "D26") (pin "1") (pinfunction "K_1") (pintype "passive"))
      (node (ref "D27") (pin "1") (pinfunction "K_1") (pintype "passive"))
      (node (ref "D28") (pin "1") (pinfunction "K_1") (pintype "passive"))
      (node (ref "D29") (pin "1") (pinfunction "K_1") (pintype "passive"))
      (node (ref "D3") (pin "1") (pinfunction "K_1") (pintype "passive"))
      (node (ref "D30") (pin "1") (pinfunction "K_1") (pintype "passive"))
      (node (ref "D31") (pin "1") (pinfunction "K_1") (pintype "passive"))
      (node (ref "D32") (pin "1") (pinfunction "K_1") (pintype "passive"))
      (node (ref "D33") (pin "1") (pinfunction "K_1") (pintype "passive"))
      (node (ref "D34") (pin "1") (pinfunction "K_1") (pintype "passive"))
      (node (ref "D35") (pin "1") (pinfunction "K_1") (pintype "passive"))
      (node (ref "D36") (pin "1") (pinfunction "K_1") (pintype "passive"))
      (node (ref "D37") (pin "1") (pinfunction "K_1") (pintype "passive"))
      (node (ref "D38") (pin "1") (pinfunction "K_1") (pintype "passive"))
      (node (ref "D39") (pin "1") (pinfunction "K_1") (pintype "passive"))
      (node (ref "D4") (pin "1") (pinfunction "K_1") (pintype "passive"))
      (node (ref "D40") (pin "1") (pinfunction "K_1") (pintype "passive"))
      (node (ref "D41") (pin "1") (pinfunction "K_1") (pintype "passive"))
      (node (ref "D42") (pin "1") (pinfunction "K_1") (pintype "passive"))
      (node (ref "D43") (pin "1") (pinfunction "K_1") (pintype "passive"))
      (node (ref "D44") (pin "1") (pinfunction "K_1") (pintype "passive"))
      (node (ref "D45") (pin "1") (pinfunction "K_1") (pintype "passive"))
      (node (ref "D46") (pin "1") (pinfunction "K_1") (pintype "passive"))
      (node (ref "D47") (pin "1") (pinfunction "K_1") (pintype "passive"))
      (node (ref "D48") (pin "1") (pinfunction "K_1") (pintype "passive"))
      (node (ref "D49") (pin "1") (pinfunction "K_1") (pintype "passive"))
      (node (ref "D5") (pin "1") (pinfunction "K_1") (pintype "passive"))
      (node (ref "D6") (pin "1") (pinfunction "K_1") (pintype "passive"))
      (node (ref "D7") (pin "1") (pinfunction "K_1") (pintype "passive"))
      (node (ref "D8") (pin "1") (pinfunction "K_1") (pintype "passive"))
      (node (ref "D9") (pin "1") (pinfunction "K_1") (pintype "passive"))
      (node (ref "J1") (pin "2") (pinfunction "2_2") (pintype "passive"))
    )
    (net (code "3") (name "Net-(D1-A)") (class "Default")
      (node (ref "D1") (pin "2") (pinfunction "A_2") (pintype "passive"))
      (node (ref "R1") (pin "1") (pinfunction "1_1") (pintype "passive"))
    )
    (net (code "4") (name "Net-(D2-A)") (class "Default")
      (node (ref "D2") (pin "2") (pinfunction "A_2") (pintype "passive"))
      (node (ref "R3") (pin "1") (pinfunction "1_1") (pintype "passive"))
    )
    (net (code "5") (name "Net-(D3-A)") (class "Default")
      (node (ref "D3") (pin "2") (pinfunction "A_2") (pintype "passive"))
      (node (ref "R4") (pin "1") (pinfunction "1_1") (pintype "passive"))
    )
    (net (code "6") (name "Net-(D4-A)") (class "Default")
      (node (ref "D4") (pin "2") (pinfunction "A_2") (pintype "passive"))
      (node (ref "R5") (pin "1") (pinfunction "1_1") (pintype "passive"))
    )
    (net (code "7") (name "Net-(D5-A)") (class "Default")
      (node (ref "D5") (pin "2") (pinfunction "A_2") (pintype "passive"))
      (node (ref "R6") (pin "1") (pinfunction "1_1") (pintype "passive"))
    )
    (net (code "8") (name "Net-(D6-A)") (class "Default")
      (node (ref "D6") (pin "2") (pinfunction "A_2") (pintype "passive"))
      (node (ref "R7") (pin "1") (pinfunction "1_1") (pintype "passive"))
    )
    (net (code "9") (name "Net-(D7-A)") (class "Default")
      (node (ref "D7") (pin "2") (pinfunction "A_2") (pintype "passive"))
      (node (ref "R2") (pin "1") (pinfunction "1_1") (pintype "passive"))
    )
    (net (code "10") (name "Net-(D8-A)") (class "Default")
      (node (ref "D8") (pin "2") (pinfunction "A_2") (pintype "passive"))
      (node (ref "R8") (pin "1") (pinfunction "1_1") (pintype "passive"))
    )
    (net (code "11") (name "Net-(D9-A)") (class "Default")
      (node (ref "D9") (pin "2") (pinfunction "A_2") (pintype "passive"))
      (node (ref "R9") (pin "1") (pinfunction "1_1") (pintype "passive"))
    )
    (net (code "12") (name "Net-(D10-A)") (class "Default")
      (node (ref "D10") (pin "2") (pinfunction "A_2") (pintype "passive"))
      (node (ref "R10") (pin "1") (pinfunction "1_1") (pintype "passive"))
    )
    (net (code "13") (name "Net-(D11-A)") (class "Default")
      (node (ref "D11") (pin "2") (pinfunction "A_2") (pintype "passive"))
      (node (ref "R11") (pin "1") (pinfunction "1_1") (pintype "passive"))
    )
    (net (code "14") (name "Net-(D12-A)") (class "Default")
      (node (ref "D12") (pin "2") (pinfunction "A_2") (pintype "passive"))
      (node (ref "R13") (pin "1") (pinfunction "1_1") (pintype "passive"))
    )
    (net (code "15") (name "Net-(D13-A)") (class "Default")
      (node (ref "D13") (pin "2") (pinfunction "A_2") (pintype "passive"))
      (node (ref "R14") (pin "1") (pinfunction "1_1") (pintype "passive"))
    )
    (net (code "16") (name "Net-(D14-A)") (class "Default")
      (node (ref "D14") (pin "2") (pinfunction "A_2") (pintype "passive"))
      (node (ref "R15") (pin "1") (pinfunction "1_1") (pintype "passive"))
    )
    (net (code "17") (name "Net-(D15-A)") (class "Default")
      (node (ref "D15") (pin "2") (pinfunction "A_2") (pintype "passive"))
      (node (ref "R16") (pin "1") (pinfunction "1_1") (pintype "passive"))
    )
    (net (code "18") (name "Net-(D16-A)") (class "Default")
      (node (ref "D16") (pin "2") (pinfunction "A_2") (pintype "passive"))
      (node (ref "R17") (pin "1") (pinfunction "1_1") (pintype "passive"))
    )
    (net (code "19") (name "Net-(D17-A)") (class "Default")
      (node (ref "D17") (pin "2") (pinfunction "A_2") (pintype "passive"))
      (node (ref "R12") (pin "1") (pinfunction "1_1") (pintype "passive"))
    )
    (net (code "20") (name "Net-(D18-A)") (class "Default")
      (node (ref "D18") (pin "2") (pinfunction "A_2") (pintype "passive"))
      (node (ref "R18") (pin "1") (pinfunction "1_1") (pintype "passive"))
    )
    (net (code "21") (name "Net-(D19-A)") (class "Default")
      (node (ref "D19") (pin "2") (pinfunction "A_2") (pintype "passive"))
      (node (ref "R19") (pin "1") (pinfunction "1_1") (pintype "passive"))
    )
    (net (code "22") (name "Net-(D20-A)") (class "Default")
      (node (ref "D20") (pin "2") (pinfunction "A_2") (pintype "passive"))
      (node (ref "R20") (pin "1") (pinfunction "1_1") (pintype "passive"))
    )
    (net (code "23") (name "Net-(D21-A)") (class "Default")
      (node (ref "D21") (pin "2") (pinfunction "A_2") (pintype "passive"))
      (node (ref "R21") (pin "1") (pinfunction "1_1") (pintype "passive"))
    )
    (net (code "24") (name "Net-(D22-A)") (class "Default")
      (node (ref "D22") (pin "2") (pinfunction "A_2") (pintype "passive"))
      (node (ref "R23") (pin "1") (pinfunction "1_1") (pintype "passive"))
    )
    (net (code "25") (name "Net-(D23-A)") (class "Default")
      (node (ref "D23") (pin "2") (pinfunction "A_2") (pintype "passive"))
      (node (ref "R24") (pin "1") (pinfunction "1_1") (pintype "passive"))
    )
    (net (code "26") (name "Net-(D24-A)") (class "Default")
      (node (ref "D24") (pin "2") (pinfunction "A_2") (pintype "passive"))
      (node (ref "R25") (pin "1") (pinfunction "1_1") (pintype "passive"))
    )
    (net (code "27") (name "Net-(D25-A)") (class "Default")
      (node (ref "D25") (pin "2") (pinfunction "A_2") (pintype "passive"))
      (node (ref "R26") (pin "1") (pinfunction "1_1") (pintype "passive"))
    )
    (net (code "28") (name "Net-(D26-A)") (class "Default")
      (node (ref "D26") (pin "2") (pinfunction "A_2") (pintype "passive"))
      (node (ref "R27") (pin "1") (pinfunction "1_1") (pintype "passive"))
    )
    (net (code "29") (name "Net-(D27-A)") (class "Default")
      (node (ref "D27") (pin "2") (pinfunction "A_2") (pintype "passive"))
      (node (ref "R22") (pin "1") (pinfunction "1_1") (pintype "passive"))
    )
    (net (code "30") (name "Net-(D28-A)") (class "Default")
      (node (ref "D28") (pin "2") (pinfunction "A_2") (pintype "passive"))
      (node (ref "R28") (pin "1") (pinfunction "1_1") (pintype "passive"))
    )
    (net (code "31") (name "Net-(D29-A)") (class "Default")
      (node (ref "D29") (pin "2") (pinfunction "A_2") (pintype "passive"))
      (node (ref "R29") (pin "1") (pinfunction "1_1") (pintype "passive"))
    )
    (net (code "32") (name "Net-(D30-A)") (class "Default")
      (node (ref "D30") (pin "2") (pinfunction "A_2") (pintype "passive"))
      (node (ref "R30") (pin "1") (pinfunction "1_1") (pintype "passive"))
    )
    (net (code "33") (name "Net-(D31-A)") (class "Default")
      (node (ref "D31") (pin "2") (pinfunction "A_2") (pintype "passive"))
      (node (ref "R31") (pin "1") (pinfunction "1_1") (pintype "passive"))
    )
    (net (code "34") (name "Net-(D32-A)") (class "Default")
      (node (ref "D32") (pin "2") (pinfunction "A_2") (pintype "passive"))
      (node (ref "R33") (pin "1") (pinfunction "1_1") (pintype "passive"))
    )
    (net (code "35") (name "Net-(D33-A)") (class "Default")
      (node (ref "D33") (pin "2") (pinfunction "A_2") (pintype "passive"))
      (node (ref "R34") (pin "1") (pinfunction "1_1") (pintype "passive"))
    )
    (net (code "36") (name "Net-(D34-A)") (class "Default")
      (node (ref "D34") (pin "2") (pinfunction "A_2") (pintype "passive"))
      (node (ref "R35") (pin "1") (pinfunction "1_1") (pintype "passive"))
    )
    (net (code "37") (name "Net-(D35-A)") (class "Default")
      (node (ref "D35") (pin "2") (pinfunction "A_2") (pintype "passive"))
      (node (ref "R36") (pin "1") (pinfunction "1_1") (pintype "passive"))
    )
    (net (code "38") (name "Net-(D36-A)") (class "Default")
      (node (ref "D36") (pin "2") (pinfunction "A_2") (pintype "passive"))
      (node (ref "R37") (pin "1") (pinfunction "1_1") (pintype "passive"))
    )
    (net (code "39") (name "Net-(D37-A)") (class "Default")
      (node (ref "D37") (pin "2") (pinfunction "A_2") (pintype "passive"))
      (node (ref "R32") (pin "1") (pinfunction "1_1") (pintype "passive"))
    )
    (net (code "40") (name "Net-(D38-A)") (class "Default")
      (node (ref "D38") (pin "2") (pinfunction "A_2") (pintype "passive"))
      (node (ref "R38") (pin "1") (pinfunction "1_1") (pintype "passive"))
    )
    (net (code "41") (name "Net-(D39-A)") (class "Default")
      (node (ref "D39") (pin "2") (pinfunction "A_2") (pintype "passive"))
      (node (ref "R39") (pin "1") (pinfunction "1_1") (pintype "passive"))
    )
    (net (code "42") (name "Net-(D40-A)") (class "Default")
      (node (ref "D40") (pin "2") (pinfunction "A_2") (pintype "passive"))
      (node (ref "R40") (pin "1") (pinfunction "1_1") (pintype "passive"))
    )
    (net (code "43") (name "Net-(D41-A)") (class "Default")
      (node (ref "D41") (pin "2") (pinfunction "A_2") (pintype "passive"))
      (node (ref "R41") (pin "1") (pinfunction "1_1") (pintype "passive"))
    )
    (net (code "44") (name "Net-(D42-A)") (class "Default")
      (node (ref "D42") (pin "2") (pinfunction "A_2") (pintype "passive"))
      (node (ref "R43") (pin "1") (pinfunction "1_1") (pintype "passive"))
    )
    (net (code "45") (name "Net-(D43-A)") (class "Default")
      (node (ref "D43") (pin "2") (pinfunction "A_2") (pintype "passive"))
      (node (ref "R44") (pin "1") (pinfunction "1_1") (pintype "passive"))
    )
    (net (code "46") (name "Net-(D44-A)") (class "Default")
      (node (ref "D44") (pin "2") (pinfunction "A_2") (pintype "passive"))
      (node (ref "R45") (pin "1") (pinfunction "1_1") (pintype "passive"))
    )
    (net (code "47") (name "Net-(D45-A)") (class "Default")
      (node (ref "D45") (pin "2") (pinfunction "A_2") (pintype "passive"))
      (node (ref "R46") (pin "1") (pinfunction "1_1") (pintype "passive"))
    )
    (net (code "48") (name "Net-(D46-A)") (class "Default")
      (node (ref "D46") (pin "2") (pinfunction "A_2") (pintype "passive"))
      (node (ref "R47") (pin "1") (pinfunction "1_1") (pintype "passive"))
    )
    (net (code "49") (name "Net-(D47-A)") (class "Default")
      (node (ref "D47") (pin "2") (pinfunction "A_2") (pintype "passive"))
      (node (ref "R42") (pin "1") (pinfunction "1_1") (pintype "passive"))
    )
    (net (code "50") (name "Net-(D48-A)") (class "Default")
      (node (ref "D48") (pin "2") (pinfunction "A_2") (pintype "passive"))
      (node (ref "R48") (pin "1") (pinfunction "1_1") (pintype "passive"))
    )
    (net (code "51") (name "Net-(D49-A)") (class "Default")
      (node (ref "D49") (pin "2") (pinfunction "A_2") (pintype "passive"))
      (node (ref "R49") (pin "1") (pinfunction "1_1") (pintype "passive"))
    )
  )
)
